# max7219-displays.net
KiCad netlist of a schematic drawn in EAGLE
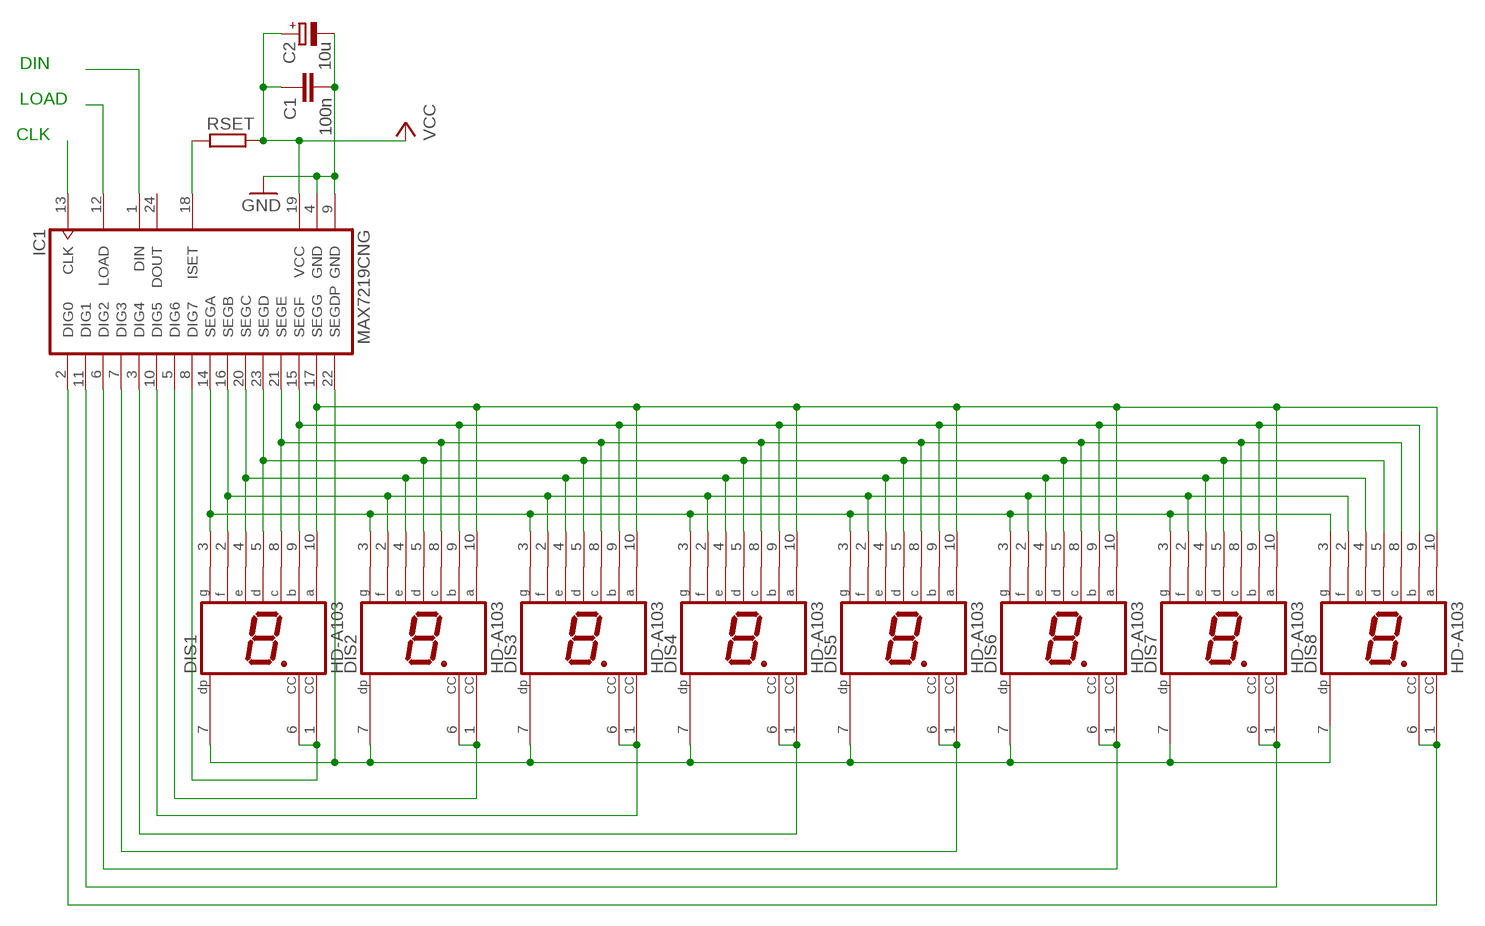
[diagram p0: schematic, sheet 1]

(export (version "E")
  (design (tool "Eeschema 10.0.6"))
  (components
    (comp (ref "C1")
      (value "100n")
      (footprint "eagle-import:C025-024X044")
      (libsource (lib "eagle-import") (part "C-EU025-024X044"))
    )
    (comp (ref "C2")
      (value "10u")
      (footprint "eagle-import:139CLL-2R")
      (libsource (lib "eagle-import") (part "CPOL-EU139CLL-2R"))
    )
    (comp (ref "DIS1")
      (value "HD-A103")
      (footprint "eagle-import:HDSP-A")
      (libsource (lib "eagle-import") (part "HD-A103"))
    )
    (comp (ref "DIS2")
      (value "HD-A103")
      (footprint "eagle-import:HDSP-A")
      (libsource (lib "eagle-import") (part "HD-A103"))
    )
    (comp (ref "DIS3")
      (value "HD-A103")
      (footprint "eagle-import:HDSP-A")
      (libsource (lib "eagle-import") (part "HD-A103"))
    )
    (comp (ref "DIS4")
      (value "HD-A103")
      (footprint "eagle-import:HDSP-A")
      (libsource (lib "eagle-import") (part "HD-A103"))
    )
    (comp (ref "DIS5")
      (value "HD-A103")
      (footprint "eagle-import:HDSP-A")
      (libsource (lib "eagle-import") (part "HD-A103"))
    )
    (comp (ref "DIS6")
      (value "HD-A103")
      (footprint "eagle-import:HDSP-A")
      (libsource (lib "eagle-import") (part "HD-A103"))
    )
    (comp (ref "DIS7")
      (value "HD-A103")
      (footprint "eagle-import:HDSP-A")
      (libsource (lib "eagle-import") (part "HD-A103"))
    )
    (comp (ref "DIS8")
      (value "HD-A103")
      (footprint "eagle-import:HDSP-A")
      (libsource (lib "eagle-import") (part "HD-A103"))
    )
    (comp (ref "IC1")
      (value "MAX7219CNG")
      (footprint "eagle-import:DIL24-3")
      (fields (field (name "MF") "MAXIM"))
      (libsource (lib "eagle-import") (part "MAX7219CNG"))
    )
    (comp (ref "RSET")
      (value "R-EU_0204/7")
      (footprint "eagle-import:0204_7")
      (libsource (lib "eagle-import") (part "R-EU_0204/7"))
    )
  )
  (nets
    (net (code "1") (name "GND") (class "Default")
      (node (ref "C1") (pin "2") (pinfunction "2_2") (pintype "passive"))
      (node (ref "C2") (pin "-") (pinfunction "-_-") (pintype "passive"))
      (node (ref "IC1") (pin "4") (pinfunction "GND_4") (pintype "power_in"))
      (node (ref "IC1") (pin "9") (pinfunction "GND_9") (pintype "power_in"))
    )
    (net (code "2") (name "Net-(DIS1-A)") (class "Default")
      (node (ref "DIS1") (pin "10") (pinfunction "A_10") (pintype "passive"))
      (node (ref "DIS2") (pin "10") (pinfunction "A_10") (pintype "passive"))
      (node (ref "DIS3") (pin "10") (pinfunction "A_10") (pintype "passive"))
      (node (ref "DIS4") (pin "10") (pinfunction "A_10") (pintype "passive"))
      (node (ref "DIS5") (pin "10") (pinfunction "A_10") (pintype "passive"))
      (node (ref "DIS6") (pin "10") (pinfunction "A_10") (pintype "passive"))
      (node (ref "DIS7") (pin "10") (pinfunction "A_10") (pintype "passive"))
      (node (ref "DIS8") (pin "10") (pinfunction "A_10") (pintype "passive"))
      (node (ref "IC1") (pin "17") (pinfunction "SEGG_17") (pintype "output"))
    )
    (net (code "3") (name "Net-(DIS1-B)") (class "Default")
      (node (ref "DIS1") (pin "9") (pinfunction "B_9") (pintype "passive"))
      (node (ref "DIS2") (pin "9") (pinfunction "B_9") (pintype "passive"))
      (node (ref "DIS3") (pin "9") (pinfunction "B_9") (pintype "passive"))
      (node (ref "DIS4") (pin "9") (pinfunction "B_9") (pintype "passive"))
      (node (ref "DIS5") (pin "9") (pinfunction "B_9") (pintype "passive"))
      (node (ref "DIS6") (pin "9") (pinfunction "B_9") (pintype "passive"))
      (node (ref "DIS7") (pin "9") (pinfunction "B_9") (pintype "passive"))
      (node (ref "DIS8") (pin "9") (pinfunction "B_9") (pintype "passive"))
      (node (ref "IC1") (pin "15") (pinfunction "SEGF_15") (pintype "output"))
    )
    (net (code "4") (name "Net-(DIS1-C)") (class "Default")
      (node (ref "DIS1") (pin "8") (pinfunction "C_8") (pintype "passive"))
      (node (ref "DIS2") (pin "8") (pinfunction "C_8") (pintype "passive"))
      (node (ref "DIS3") (pin "8") (pinfunction "C_8") (pintype "passive"))
      (node (ref "DIS4") (pin "8") (pinfunction "C_8") (pintype "passive"))
      (node (ref "DIS5") (pin "8") (pinfunction "C_8") (pintype "passive"))
      (node (ref "DIS6") (pin "8") (pinfunction "C_8") (pintype "passive"))
      (node (ref "DIS7") (pin "8") (pinfunction "C_8") (pintype "passive"))
      (node (ref "DIS8") (pin "8") (pinfunction "C_8") (pintype "passive"))
      (node (ref "IC1") (pin "21") (pinfunction "SEGE_21") (pintype "output"))
    )
    (net (code "5") (name "Net-(DIS1-D)") (class "Default")
      (node (ref "DIS1") (pin "5") (pinfunction "D_5") (pintype "passive"))
      (node (ref "DIS2") (pin "5") (pinfunction "D_5") (pintype "passive"))
      (node (ref "DIS3") (pin "5") (pinfunction "D_5") (pintype "passive"))
      (node (ref "DIS4") (pin "5") (pinfunction "D_5") (pintype "passive"))
      (node (ref "DIS5") (pin "5") (pinfunction "D_5") (pintype "passive"))
      (node (ref "DIS6") (pin "5") (pinfunction "D_5") (pintype "passive"))
      (node (ref "DIS7") (pin "5") (pinfunction "D_5") (pintype "passive"))
      (node (ref "DIS8") (pin "5") (pinfunction "D_5") (pintype "passive"))
      (node (ref "IC1") (pin "23") (pinfunction "SEGD_23") (pintype "output"))
    )
    (net (code "6") (name "Net-(DIS1-DP)") (class "Default")
      (node (ref "DIS1") (pin "7") (pinfunction "DP_7") (pintype "passive"))
      (node (ref "DIS2") (pin "7") (pinfunction "DP_7") (pintype "passive"))
      (node (ref "DIS3") (pin "7") (pinfunction "DP_7") (pintype "passive"))
      (node (ref "DIS4") (pin "7") (pinfunction "DP_7") (pintype "passive"))
      (node (ref "DIS5") (pin "7") (pinfunction "DP_7") (pintype "passive"))
      (node (ref "DIS6") (pin "7") (pinfunction "DP_7") (pintype "passive"))
      (node (ref "DIS7") (pin "7") (pinfunction "DP_7") (pintype "passive"))
      (node (ref "IC1") (pin "22") (pinfunction "SEGDP_22") (pintype "output"))
    )
    (net (code "7") (name "Net-(DIS1-E)") (class "Default")
      (node (ref "DIS1") (pin "4") (pinfunction "E_4") (pintype "passive"))
      (node (ref "DIS2") (pin "4") (pinfunction "E_4") (pintype "passive"))
      (node (ref "DIS3") (pin "4") (pinfunction "E_4") (pintype "passive"))
      (node (ref "DIS4") (pin "4") (pinfunction "E_4") (pintype "passive"))
      (node (ref "DIS5") (pin "4") (pinfunction "E_4") (pintype "passive"))
      (node (ref "DIS6") (pin "4") (pinfunction "E_4") (pintype "passive"))
      (node (ref "DIS7") (pin "4") (pinfunction "E_4") (pintype "passive"))
      (node (ref "DIS8") (pin "4") (pinfunction "E_4") (pintype "passive"))
      (node (ref "IC1") (pin "20") (pinfunction "SEGC_20") (pintype "output"))
    )
    (net (code "8") (name "Net-(DIS1-F)") (class "Default")
      (node (ref "DIS1") (pin "2") (pinfunction "F_2") (pintype "passive"))
      (node (ref "DIS2") (pin "2") (pinfunction "F_2") (pintype "passive"))
      (node (ref "DIS3") (pin "2") (pinfunction "F_2") (pintype "passive"))
      (node (ref "DIS4") (pin "2") (pinfunction "F_2") (pintype "passive"))
      (node (ref "DIS5") (pin "2") (pinfunction "F_2") (pintype "passive"))
      (node (ref "DIS6") (pin "2") (pinfunction "F_2") (pintype "passive"))
      (node (ref "DIS7") (pin "2") (pinfunction "F_2") (pintype "passive"))
      (node (ref "DIS8") (pin "2") (pinfunction "F_2") (pintype "passive"))
      (node (ref "IC1") (pin "16") (pinfunction "SEGB_16") (pintype "output"))
    )
    (net (code "9") (name "Net-(DIS1-G)") (class "Default")
      (node (ref "DIS1") (pin "3") (pinfunction "G_3") (pintype "passive"))
      (node (ref "DIS2") (pin "3") (pinfunction "G_3") (pintype "passive"))
      (node (ref "DIS3") (pin "3") (pinfunction "G_3") (pintype "passive"))
      (node (ref "DIS4") (pin "3") (pinfunction "G_3") (pintype "passive"))
      (node (ref "DIS5") (pin "3") (pinfunction "G_3") (pintype "passive"))
      (node (ref "DIS6") (pin "3") (pinfunction "G_3") (pintype "passive"))
      (node (ref "DIS7") (pin "3") (pinfunction "G_3") (pintype "passive"))
      (node (ref "DIS8") (pin "3") (pinfunction "G_3") (pintype "passive"))
      (node (ref "IC1") (pin "14") (pinfunction "SEGA_14") (pintype "output"))
    )
    (net (code "10") (name "Net-(IC1-DIG0)") (class "Default")
      (node (ref "DIS8") (pin "1") (pinfunction "CC_1") (pintype "passive"))
      (node (ref "DIS8") (pin "6") (pinfunction "CC_6") (pintype "passive"))
      (node (ref "IC1") (pin "2") (pinfunction "DIG0_2") (pintype "output"))
    )
    (net (code "11") (name "Net-(IC1-DIG1)") (class "Default")
      (node (ref "DIS7") (pin "1") (pinfunction "CC_1") (pintype "passive"))
      (node (ref "DIS7") (pin "6") (pinfunction "CC_6") (pintype "passive"))
      (node (ref "IC1") (pin "11") (pinfunction "DIG1_11") (pintype "output"))
    )
    (net (code "12") (name "Net-(IC1-DIG2)") (class "Default")
      (node (ref "DIS6") (pin "1") (pinfunction "CC_1") (pintype "passive"))
      (node (ref "DIS6") (pin "6") (pinfunction "CC_6") (pintype "passive"))
      (node (ref "IC1") (pin "6") (pinfunction "DIG2_6") (pintype "output"))
    )
    (net (code "13") (name "Net-(IC1-DIG3)") (class "Default")
      (node (ref "DIS5") (pin "1") (pinfunction "CC_1") (pintype "passive"))
      (node (ref "DIS5") (pin "6") (pinfunction "CC_6") (pintype "passive"))
      (node (ref "IC1") (pin "7") (pinfunction "DIG3_7") (pintype "output"))
    )
    (net (code "14") (name "Net-(IC1-DIG4)") (class "Default")
      (node (ref "DIS4") (pin "1") (pinfunction "CC_1") (pintype "passive"))
      (node (ref "DIS4") (pin "6") (pinfunction "CC_6") (pintype "passive"))
      (node (ref "IC1") (pin "3") (pinfunction "DIG4_3") (pintype "output"))
    )
    (net (code "15") (name "Net-(IC1-DIG5)") (class "Default")
      (node (ref "DIS3") (pin "1") (pinfunction "CC_1") (pintype "passive"))
      (node (ref "DIS3") (pin "6") (pinfunction "CC_6") (pintype "passive"))
      (node (ref "IC1") (pin "10") (pinfunction "DIG5_10") (pintype "output"))
    )
    (net (code "16") (name "Net-(IC1-DIG6)") (class "Default")
      (node (ref "DIS2") (pin "1") (pinfunction "CC_1") (pintype "passive"))
      (node (ref "DIS2") (pin "6") (pinfunction "CC_6") (pintype "passive"))
      (node (ref "IC1") (pin "5") (pinfunction "DIG6_5") (pintype "output"))
    )
    (net (code "17") (name "Net-(IC1-DIG7)") (class "Default")
      (node (ref "DIS1") (pin "1") (pinfunction "CC_1") (pintype "passive"))
      (node (ref "DIS1") (pin "6") (pinfunction "CC_6") (pintype "passive"))
      (node (ref "IC1") (pin "8") (pinfunction "DIG7_8") (pintype "output"))
    )
    (net (code "18") (name "Net-(IC1-ISET)") (class "Default")
      (node (ref "IC1") (pin "18") (pinfunction "ISET_18") (pintype "input"))
      (node (ref "RSET") (pin "2") (pinfunction "2_2") (pintype "passive"))
    )
    (net (code "19") (name "VCC") (class "Default")
      (node (ref "C1") (pin "1") (pinfunction "1_1") (pintype "passive"))
      (node (ref "C2") (pin "+") (pinfunction "+_+") (pintype "passive"))
      (node (ref "IC1") (pin "19") (pinfunction "VCC_19") (pintype "power_in"))
      (node (ref "RSET") (pin "1") (pinfunction "1_1") (pintype "passive"))
    )
    (net (code "20") (name "unconnected-(DIS8-DP-Pad7)") (class "Default")
      (node (ref "DIS8") (pin "7") (pinfunction "DP_7") (pintype "passive"))
    )
    (net (code "21") (name "unconnected-(IC1-CLK-Pad13)") (class "Default")
      (node (ref "IC1") (pin "13") (pinfunction "CLK_13") (pintype "input"))
    )
    (net (code "22") (name "unconnected-(IC1-DIN-Pad1)") (class "Default")
      (node (ref "IC1") (pin "1") (pinfunction "DIN_1") (pintype "input"))
    )
    (net (code "23") (name "unconnected-(IC1-DOUT-Pad24)") (class "Default")
      (node (ref "IC1") (pin "24") (pinfunction "DOUT_24") (pintype "output"))
    )
    (net (code "24") (name "unconnected-(IC1-LOAD-Pad12)") (class "Default")
      (node (ref "IC1") (pin "12") (pinfunction "LOAD_12") (pintype "input"))
    )
  )
)
